# control_board.net
KiCad netlist of a schematic drawn in EAGLE
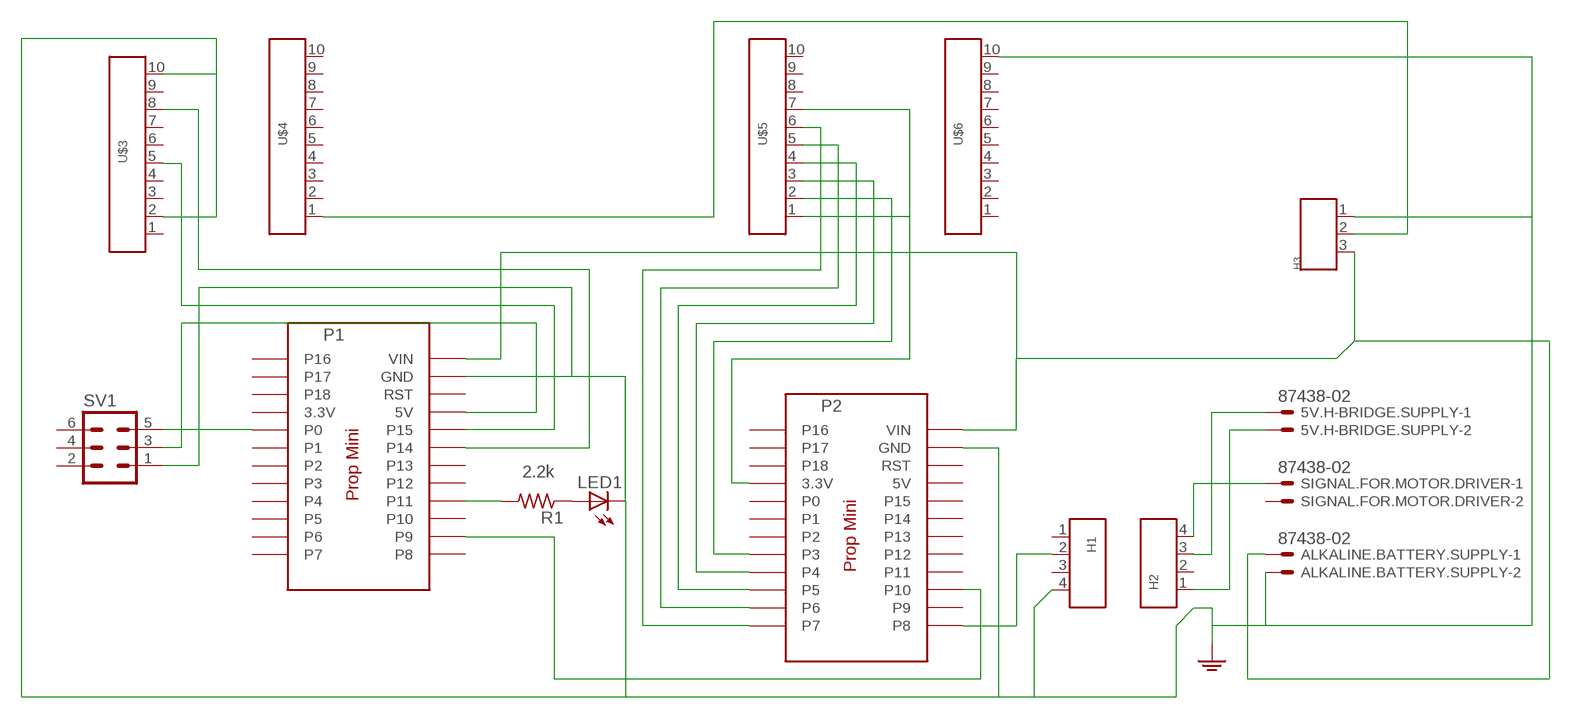
[diagram p0: schematic, sheet 1]

(export (version "E")
  (design (tool "Eeschema 10.0.6"))
  (components
    (comp (ref "5V.H-BRIDGE.SUPPLY")
      (value "87438-02")
      (footprint "eagle-import:87438-02")
      (libsource (lib "eagle-import") (part "87438-02"))
    )
    (comp (ref "ALKALINE.BATTERY.SUPPLY")
      (value "87438-02")
      (footprint "eagle-import:87438-02")
      (libsource (lib "eagle-import") (part "87438-02"))
    )
    (comp (ref "H1")
      (value "1X04")
      (footprint "eagle-import:DIP0.1-1X04")
      (libsource (lib "eagle-import") (part "1X04"))
    )
    (comp (ref "H2")
      (value "1X04")
      (footprint "eagle-import:DIP0.1-1X04")
      (libsource (lib "eagle-import") (part "1X04"))
    )
    (comp (ref "H3")
      (value "1X03")
      (footprint "eagle-import:DIP0.1-1X03")
      (libsource (lib "eagle-import") (part "1X03"))
    )
    (comp (ref "LED1")
      (value "LED3MM")
      (footprint "eagle-import:LED3MM")
      (libsource (lib "eagle-import") (part "LED3MM"))
    )
    (comp (ref "P1")
      (value "PROP-MINI")
      (footprint "eagle-import:PROP-MINI")
      (libsource (lib "eagle-import") (part "PROP-MINI"))
    )
    (comp (ref "P2")
      (value "PROP-MINI")
      (footprint "eagle-import:PROP-MINI")
      (libsource (lib "eagle-import") (part "PROP-MINI"))
    )
    (comp (ref "R1")
      (value "R0603")
      (footprint "eagle-import:0603")
      (fields (field (name "R1") "2.2k"))
      (libsource (lib "eagle-import") (part "R0603"))
    )
    (comp (ref "SIGNAL.FOR.MOTOR.DRIVER")
      (value "87438-02")
      (footprint "eagle-import:87438-02")
      (libsource (lib "eagle-import") (part "87438-02"))
    )
    (comp (ref "SV1")
      (value "MA03-2")
      (footprint "eagle-import:MA03-2")
      (libsource (lib "eagle-import") (part "MA03-2"))
    )
    (comp (ref "U$3")
      (value "1X10")
      (footprint "eagle-import:DIP0.1-1X10")
      (libsource (lib "eagle-import") (part "1X10"))
    )
    (comp (ref "U$4")
      (value "1X10")
      (footprint "eagle-import:DIP0.1-1X10")
      (libsource (lib "eagle-import") (part "1X10"))
    )
    (comp (ref "U$5")
      (value "1X10")
      (footprint "eagle-import:DIP0.1-1X10")
      (libsource (lib "eagle-import") (part "1X10"))
    )
    (comp (ref "U$6")
      (value "1X10")
      (footprint "eagle-import:DIP0.1-1X10")
      (libsource (lib "eagle-import") (part "1X10"))
    )
  )
  (nets
    (net (code "1") (name "GND") (class "Default")
      (node (ref "ALKALINE.BATTERY.SUPPLY") (pin "2") (pinfunction "S_2") (pintype "passive"))
      (node (ref "H1") (pin "4") (pinfunction "4_4") (pintype "bidirectional"))
      (node (ref "H3") (pin "1") (pinfunction "1_1") (pintype "bidirectional"))
      (node (ref "P2") (pin "GND") (pinfunction "GND_GND") (pintype "bidirectional"))
      (node (ref "U$3") (pin "10") (pinfunction "10_10") (pintype "bidirectional"))
      (node (ref "U$3") (pin "2") (pinfunction "2_2") (pintype "bidirectional"))
      (node (ref "U$6") (pin "10") (pinfunction "10_10") (pintype "bidirectional"))
    )
    (net (code "2") (name "Net-(5V.H-BRIDGE.SUPPLYA-S)") (class "Default")
      (node (ref "5V.H-BRIDGE.SUPPLY") (pin "1") (pinfunction "S_1") (pintype "passive"))
      (node (ref "H2") (pin "3") (pinfunction "3_3") (pintype "bidirectional"))
    )
    (net (code "3") (name "Net-(5V.H-BRIDGE.SUPPLYB-S)") (class "Default")
      (node (ref "5V.H-BRIDGE.SUPPLY") (pin "2") (pinfunction "S_2") (pintype "passive"))
      (node (ref "H2") (pin "1") (pinfunction "1_1") (pintype "bidirectional"))
    )
    (net (code "4") (name "Net-(ALKALINE.BATTERY.SUPPLYA-S)") (class "Default")
      (node (ref "ALKALINE.BATTERY.SUPPLY") (pin "1") (pinfunction "S_1") (pintype "passive"))
      (node (ref "H3") (pin "3") (pinfunction "3_3") (pintype "bidirectional"))
      (node (ref "P1") (pin "VIN") (pinfunction "VIN_VIN") (pintype "bidirectional"))
      (node (ref "P2") (pin "VIN") (pinfunction "VIN_VIN") (pintype "bidirectional"))
    )
    (net (code "5") (name "Net-(H1-Pad2)") (class "Default")
      (node (ref "H1") (pin "2") (pinfunction "2_2") (pintype "bidirectional"))
      (node (ref "P2") (pin "P8") (pinfunction "P8_P8") (pintype "bidirectional"))
    )
    (net (code "6") (name "Net-(H3-Pad2)") (class "Default")
      (node (ref "H3") (pin "2") (pinfunction "2_2") (pintype "bidirectional"))
      (node (ref "U$4") (pin "1") (pinfunction "1_1") (pintype "bidirectional"))
    )
    (net (code "7") (name "Net-(LED1-C)") (class "Default")
      (node (ref "LED1") (pin "K") (pinfunction "C_K") (pintype "passive"))
      (node (ref "P1") (pin "GND") (pinfunction "GND_GND") (pintype "bidirectional"))
      (node (ref "SV1") (pin "1") (pinfunction "1_1") (pintype "passive"))
    )
    (net (code "8") (name "Net-(P1-Pad5V)") (class "Default")
      (node (ref "P1") (pin "5V") (pinfunction "5V_5V") (pintype "bidirectional"))
      (node (ref "SV1") (pin "3") (pinfunction "3_3") (pintype "passive"))
    )
    (net (code "9") (name "Net-(P1-PadP0)") (class "Default")
      (node (ref "P1") (pin "P0") (pinfunction "P0_P0") (pintype "bidirectional"))
      (node (ref "SV1") (pin "5") (pinfunction "5_5") (pintype "passive"))
    )
    (net (code "10") (name "Net-(P1-PadP9)") (class "Default")
      (node (ref "P1") (pin "P9") (pinfunction "P9_P9") (pintype "bidirectional"))
      (node (ref "P2") (pin "P10") (pinfunction "P10_P10") (pintype "bidirectional"))
    )
    (net (code "11") (name "Net-(P1-PadP14)") (class "Default")
      (node (ref "P1") (pin "P14") (pinfunction "P14_P14") (pintype "bidirectional"))
      (node (ref "U$3") (pin "8") (pinfunction "8_8") (pintype "bidirectional"))
    )
    (net (code "12") (name "Net-(P1-PadP15)") (class "Default")
      (node (ref "P1") (pin "P15") (pinfunction "P15_P15") (pintype "bidirectional"))
      (node (ref "U$3") (pin "5") (pinfunction "5_5") (pintype "bidirectional"))
    )
    (net (code "13") (name "Net-(P2-Pad3.3V)") (class "Default")
      (node (ref "P2") (pin "3.3V") (pinfunction "3.3V_3.3V") (pintype "bidirectional"))
      (node (ref "U$5") (pin "1") (pinfunction "1_1") (pintype "bidirectional"))
      (node (ref "U$5") (pin "7") (pinfunction "7_7") (pintype "bidirectional"))
    )
    (net (code "14") (name "Net-(P2-PadP3)") (class "Default")
      (node (ref "P2") (pin "P3") (pinfunction "P3_P3") (pintype "bidirectional"))
      (node (ref "U$5") (pin "2") (pinfunction "2_2") (pintype "bidirectional"))
    )
    (net (code "15") (name "Net-(P2-PadP4)") (class "Default")
      (node (ref "P2") (pin "P4") (pinfunction "P4_P4") (pintype "bidirectional"))
      (node (ref "U$5") (pin "3") (pinfunction "3_3") (pintype "bidirectional"))
    )
    (net (code "16") (name "Net-(P2-PadP5)") (class "Default")
      (node (ref "P2") (pin "P5") (pinfunction "P5_P5") (pintype "bidirectional"))
      (node (ref "U$5") (pin "4") (pinfunction "4_4") (pintype "bidirectional"))
    )
    (net (code "17") (name "Net-(P2-PadP6)") (class "Default")
      (node (ref "P2") (pin "P6") (pinfunction "P6_P6") (pintype "bidirectional"))
      (node (ref "U$5") (pin "5") (pinfunction "5_5") (pintype "bidirectional"))
    )
    (net (code "18") (name "Net-(P2-PadP7)") (class "Default")
      (node (ref "P2") (pin "P7") (pinfunction "P7_P7") (pintype "bidirectional"))
      (node (ref "U$5") (pin "6") (pinfunction "6_6") (pintype "bidirectional"))
    )
    (net (code "19") (name "Net-(R1-P$1)") (class "Default")
      (node (ref "LED1") (pin "A") (pinfunction "A_A") (pintype "passive"))
      (node (ref "R1") (pin "1") (pinfunction "P$1_1") (pintype "bidirectional"))
    )
    (net (code "20") (name "Net-(R1-P$2)") (class "Default")
      (node (ref "P1") (pin "P11") (pinfunction "P11_P11") (pintype "bidirectional"))
      (node (ref "R1") (pin "2") (pinfunction "P$2_2") (pintype "bidirectional"))
    )
    (net (code "21") (name "Net-(SIGNAL.FOR.MOTOR.DRIVERA-S)") (class "Default")
      (node (ref "H2") (pin "4") (pinfunction "4_4") (pintype "bidirectional"))
      (node (ref "SIGNAL.FOR.MOTOR.DRIVER") (pin "1") (pinfunction "S_1") (pintype "passive"))
    )
    (net (code "22") (name "unconnected-(H1-Pad1)") (class "Default")
      (node (ref "H1") (pin "1") (pinfunction "1_1") (pintype "bidirectional"))
    )
    (net (code "23") (name "unconnected-(H1-Pad3)") (class "Default")
      (node (ref "H1") (pin "3") (pinfunction "3_3") (pintype "bidirectional"))
    )
    (net (code "24") (name "unconnected-(H2-Pad2)") (class "Default")
      (node (ref "H2") (pin "2") (pinfunction "2_2") (pintype "bidirectional"))
    )
    (net (code "25") (name "unconnected-(P1-Pad3.3V)") (class "Default")
      (node (ref "P1") (pin "3.3V") (pinfunction "3.3V_3.3V") (pintype "bidirectional"))
    )
    (net (code "26") (name "unconnected-(P1-PadP1)") (class "Default")
      (node (ref "P1") (pin "P1") (pinfunction "P1_P1") (pintype "bidirectional"))
    )
    (net (code "27") (name "unconnected-(P1-PadP2)") (class "Default")
      (node (ref "P1") (pin "P2") (pinfunction "P2_P2") (pintype "bidirectional"))
    )
    (net (code "28") (name "unconnected-(P1-PadP3)") (class "Default")
      (node (ref "P1") (pin "P3") (pinfunction "P3_P3") (pintype "bidirectional"))
    )
    (net (code "29") (name "unconnected-(P1-PadP4)") (class "Default")
      (node (ref "P1") (pin "P4") (pinfunction "P4_P4") (pintype "bidirectional"))
    )
    (net (code "30") (name "unconnected-(P1-PadP5)") (class "Default")
      (node (ref "P1") (pin "P5") (pinfunction "P5_P5") (pintype "bidirectional"))
    )
    (net (code "31") (name "unconnected-(P1-PadP6)") (class "Default")
      (node (ref "P1") (pin "P6") (pinfunction "P6_P6") (pintype "bidirectional"))
    )
    (net (code "32") (name "unconnected-(P1-PadP7)") (class "Default")
      (node (ref "P1") (pin "P7") (pinfunction "P7_P7") (pintype "bidirectional"))
    )
    (net (code "33") (name "unconnected-(P1-PadP8)") (class "Default")
      (node (ref "P1") (pin "P8") (pinfunction "P8_P8") (pintype "bidirectional"))
    )
    (net (code "34") (name "unconnected-(P1-PadP10)") (class "Default")
      (node (ref "P1") (pin "P10") (pinfunction "P10_P10") (pintype "bidirectional"))
    )
    (net (code "35") (name "unconnected-(P1-PadP12)") (class "Default")
      (node (ref "P1") (pin "P12") (pinfunction "P12_P12") (pintype "bidirectional"))
    )
    (net (code "36") (name "unconnected-(P1-PadP13)") (class "Default")
      (node (ref "P1") (pin "P13") (pinfunction "P13_P13") (pintype "bidirectional"))
    )
    (net (code "37") (name "unconnected-(P1-PadP16)") (class "Default")
      (node (ref "P1") (pin "P16") (pinfunction "P16_P16") (pintype "bidirectional"))
    )
    (net (code "38") (name "unconnected-(P1-PadP17)") (class "Default")
      (node (ref "P1") (pin "P17") (pinfunction "P17_P17") (pintype "bidirectional"))
    )
    (net (code "39") (name "unconnected-(P1-PadP18)") (class "Default")
      (node (ref "P1") (pin "P18") (pinfunction "P18_P18") (pintype "bidirectional"))
    )
    (net (code "40") (name "unconnected-(P1-PadRST)") (class "Default")
      (node (ref "P1") (pin "RST") (pinfunction "RST_RST") (pintype "bidirectional"))
    )
    (net (code "41") (name "unconnected-(P2-Pad5V)") (class "Default")
      (node (ref "P2") (pin "5V") (pinfunction "5V_5V") (pintype "bidirectional"))
    )
    (net (code "42") (name "unconnected-(P2-PadP0)") (class "Default")
      (node (ref "P2") (pin "P0") (pinfunction "P0_P0") (pintype "bidirectional"))
    )
    (net (code "43") (name "unconnected-(P2-PadP1)") (class "Default")
      (node (ref "P2") (pin "P1") (pinfunction "P1_P1") (pintype "bidirectional"))
    )
    (net (code "44") (name "unconnected-(P2-PadP2)") (class "Default")
      (node (ref "P2") (pin "P2") (pinfunction "P2_P2") (pintype "bidirectional"))
    )
    (net (code "45") (name "unconnected-(P2-PadP9)") (class "Default")
      (node (ref "P2") (pin "P9") (pinfunction "P9_P9") (pintype "bidirectional"))
    )
    (net (code "46") (name "unconnected-(P2-PadP11)") (class "Default")
      (node (ref "P2") (pin "P11") (pinfunction "P11_P11") (pintype "bidirectional"))
    )
    (net (code "47") (name "unconnected-(P2-PadP12)") (class "Default")
      (node (ref "P2") (pin "P12") (pinfunction "P12_P12") (pintype "bidirectional"))
    )
    (net (code "48") (name "unconnected-(P2-PadP13)") (class "Default")
      (node (ref "P2") (pin "P13") (pinfunction "P13_P13") (pintype "bidirectional"))
    )
    (net (code "49") (name "unconnected-(P2-PadP14)") (class "Default")
      (node (ref "P2") (pin "P14") (pinfunction "P14_P14") (pintype "bidirectional"))
    )
    (net (code "50") (name "unconnected-(P2-PadP15)") (class "Default")
      (node (ref "P2") (pin "P15") (pinfunction "P15_P15") (pintype "bidirectional"))
    )
    (net (code "51") (name "unconnected-(P2-PadP16)") (class "Default")
      (node (ref "P2") (pin "P16") (pinfunction "P16_P16") (pintype "bidirectional"))
    )
    (net (code "52") (name "unconnected-(P2-PadP17)") (class "Default")
      (node (ref "P2") (pin "P17") (pinfunction "P17_P17") (pintype "bidirectional"))
    )
    (net (code "53") (name "unconnected-(P2-PadP18)") (class "Default")
      (node (ref "P2") (pin "P18") (pinfunction "P18_P18") (pintype "bidirectional"))
    )
    (net (code "54") (name "unconnected-(P2-PadRST)") (class "Default")
      (node (ref "P2") (pin "RST") (pinfunction "RST_RST") (pintype "bidirectional"))
    )
    (net (code "55") (name "unconnected-(SIGNAL.FOR.MOTOR.DRIVERB-S-Pad2)") (class "Default")
      (node (ref "SIGNAL.FOR.MOTOR.DRIVER") (pin "2") (pinfunction "S_2") (pintype "passive"))
    )
    (net (code "56") (name "unconnected-(SV1-Pad2)") (class "Default")
      (node (ref "SV1") (pin "2") (pinfunction "2_2") (pintype "passive"))
    )
    (net (code "57") (name "unconnected-(SV1-Pad4)") (class "Default")
      (node (ref "SV1") (pin "4") (pinfunction "4_4") (pintype "passive"))
    )
    (net (code "58") (name "unconnected-(SV1-Pad6)") (class "Default")
      (node (ref "SV1") (pin "6") (pinfunction "6_6") (pintype "passive"))
    )
    (net (code "59") (name "unconnected-(U$3-Pad1)") (class "Default")
      (node (ref "U$3") (pin "1") (pinfunction "1_1") (pintype "bidirectional"))
    )
    (net (code "60") (name "unconnected-(U$3-Pad3)") (class "Default")
      (node (ref "U$3") (pin "3") (pinfunction "3_3") (pintype "bidirectional"))
    )
    (net (code "61") (name "unconnected-(U$3-Pad4)") (class "Default")
      (node (ref "U$3") (pin "4") (pinfunction "4_4") (pintype "bidirectional"))
    )
    (net (code "62") (name "unconnected-(U$3-Pad6)") (class "Default")
      (node (ref "U$3") (pin "6") (pinfunction "6_6") (pintype "bidirectional"))
    )
    (net (code "63") (name "unconnected-(U$3-Pad7)") (class "Default")
      (node (ref "U$3") (pin "7") (pinfunction "7_7") (pintype "bidirectional"))
    )
    (net (code "64") (name "unconnected-(U$3-Pad9)") (class "Default")
      (node (ref "U$3") (pin "9") (pinfunction "9_9") (pintype "bidirectional"))
    )
    (net (code "65") (name "unconnected-(U$4-Pad2)") (class "Default")
      (node (ref "U$4") (pin "2") (pinfunction "2_2") (pintype "bidirectional"))
    )
    (net (code "66") (name "unconnected-(U$4-Pad3)") (class "Default")
      (node (ref "U$4") (pin "3") (pinfunction "3_3") (pintype "bidirectional"))
    )
    (net (code "67") (name "unconnected-(U$4-Pad4)") (class "Default")
      (node (ref "U$4") (pin "4") (pinfunction "4_4") (pintype "bidirectional"))
    )
    (net (code "68") (name "unconnected-(U$4-Pad5)") (class "Default")
      (node (ref "U$4") (pin "5") (pinfunction "5_5") (pintype "bidirectional"))
    )
    (net (code "69") (name "unconnected-(U$4-Pad6)") (class "Default")
      (node (ref "U$4") (pin "6") (pinfunction "6_6") (pintype "bidirectional"))
    )
    (net (code "70") (name "unconnected-(U$4-Pad7)") (class "Default")
      (node (ref "U$4") (pin "7") (pinfunction "7_7") (pintype "bidirectional"))
    )
    (net (code "71") (name "unconnected-(U$4-Pad8)") (class "Default")
      (node (ref "U$4") (pin "8") (pinfunction "8_8") (pintype "bidirectional"))
    )
    (net (code "72") (name "unconnected-(U$4-Pad9)") (class "Default")
      (node (ref "U$4") (pin "9") (pinfunction "9_9") (pintype "bidirectional"))
    )
    (net (code "73") (name "unconnected-(U$4-Pad10)") (class "Default")
      (node (ref "U$4") (pin "10") (pinfunction "10_10") (pintype "bidirectional"))
    )
    (net (code "74") (name "unconnected-(U$5-Pad8)") (class "Default")
      (node (ref "U$5") (pin "8") (pinfunction "8_8") (pintype "bidirectional"))
    )
    (net (code "75") (name "unconnected-(U$5-Pad9)") (class "Default")
      (node (ref "U$5") (pin "9") (pinfunction "9_9") (pintype "bidirectional"))
    )
    (net (code "76") (name "unconnected-(U$5-Pad10)") (class "Default")
      (node (ref "U$5") (pin "10") (pinfunction "10_10") (pintype "bidirectional"))
    )
    (net (code "77") (name "unconnected-(U$6-Pad1)") (class "Default")
      (node (ref "U$6") (pin "1") (pinfunction "1_1") (pintype "bidirectional"))
    )
    (net (code "78") (name "unconnected-(U$6-Pad2)") (class "Default")
      (node (ref "U$6") (pin "2") (pinfunction "2_2") (pintype "bidirectional"))
    )
    (net (code "79") (name "unconnected-(U$6-Pad3)") (class "Default")
      (node (ref "U$6") (pin "3") (pinfunction "3_3") (pintype "bidirectional"))
    )
    (net (code "80") (name "unconnected-(U$6-Pad4)") (class "Default")
      (node (ref "U$6") (pin "4") (pinfunction "4_4") (pintype "bidirectional"))
    )
    (net (code "81") (name "unconnected-(U$6-Pad5)") (class "Default")
      (node (ref "U$6") (pin "5") (pinfunction "5_5") (pintype "bidirectional"))
    )
    (net (code "82") (name "unconnected-(U$6-Pad6)") (class "Default")
      (node (ref "U$6") (pin "6") (pinfunction "6_6") (pintype "bidirectional"))
    )
    (net (code "83") (name "unconnected-(U$6-Pad7)") (class "Default")
      (node (ref "U$6") (pin "7") (pinfunction "7_7") (pintype "bidirectional"))
    )
    (net (code "84") (name "unconnected-(U$6-Pad8)") (class "Default")
      (node (ref "U$6") (pin "8") (pinfunction "8_8") (pintype "bidirectional"))
    )
    (net (code "85") (name "unconnected-(U$6-Pad9)") (class "Default")
      (node (ref "U$6") (pin "9") (pinfunction "9_9") (pintype "bidirectional"))
    )
  )
)
